# elec_connector.net
KiCad netlist of a schematic drawn in Altium Designer
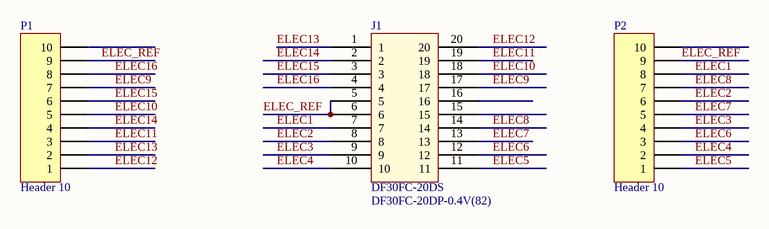
[diagram p0: elec_connector.SchDoc]

(export (version "E")
  (design (tool "Eeschema 10.0.6"))
  (components
    (comp (ref "J1")
      (value "DF30FC-20DS")
      (footprint "DF30FC-20DS")
      (description "CONN PLUG 20POS 0.4MM SMD GOLD")
      (fields
        (field (name "MANUFACTURER") "Hirose Electric Co Ltd")
        (field (name "MANUFACTURER PART NUMBER") "DF30FC-20DP-0.4V(82)")
      )
      (libsource (lib "custom") (part "DF30FC-20DP"))
    )
    (comp (ref "P1")
      (value "Header 10")
      (footprint "HDR1X10H")
      (description "Header, 10-Pin")
      (fields (field (name "PUBLISHER") "Altium Limited"))
      (libsource (lib "Miscellaneous Connectors") (part "Header 10"))
    )
    (comp (ref "P2")
      (value "Header 10")
      (footprint "HDR1X10")
      (description "Header, 10-Pin")
      (fields (field (name "PUBLISHER") "Altium Limited"))
      (libsource (lib "Miscellaneous Connectors") (part "Header 10"))
    )
  )
  (nets
    (net (code "1") (name "/ELEC1") (class "Default")
      (node (ref "J1") (pin "7") (pinfunction "7_7") (pintype "passive"))
      (node (ref "P2") (pin "8") (pinfunction "8_8") (pintype "passive"))
    )
    (net (code "2") (name "/ELEC2") (class "Default")
      (node (ref "J1") (pin "8") (pinfunction "8_8") (pintype "passive"))
      (node (ref "P2") (pin "6") (pinfunction "6_6") (pintype "passive"))
    )
    (net (code "3") (name "/ELEC3") (class "Default")
      (node (ref "J1") (pin "9") (pinfunction "9_9") (pintype "passive"))
      (node (ref "P2") (pin "4") (pinfunction "4_4") (pintype "passive"))
    )
    (net (code "4") (name "/ELEC4") (class "Default")
      (node (ref "J1") (pin "10") (pinfunction "10_10") (pintype "passive"))
      (node (ref "P2") (pin "2") (pinfunction "2_2") (pintype "passive"))
    )
    (net (code "5") (name "/ELEC5") (class "Default")
      (node (ref "J1") (pin "11") (pinfunction "11_11") (pintype "passive"))
      (node (ref "P2") (pin "1") (pinfunction "1_1") (pintype "passive"))
    )
    (net (code "6") (name "/ELEC6") (class "Default")
      (node (ref "J1") (pin "12") (pinfunction "12_12") (pintype "passive"))
      (node (ref "P2") (pin "3") (pinfunction "3_3") (pintype "passive"))
    )
    (net (code "7") (name "/ELEC7") (class "Default")
      (node (ref "J1") (pin "13") (pinfunction "13_13") (pintype "passive"))
      (node (ref "P2") (pin "5") (pinfunction "5_5") (pintype "passive"))
    )
    (net (code "8") (name "/ELEC8") (class "Default")
      (node (ref "J1") (pin "14") (pinfunction "14_14") (pintype "passive"))
      (node (ref "P2") (pin "7") (pinfunction "7_7") (pintype "passive"))
    )
    (net (code "9") (name "/ELEC9") (class "Default")
      (node (ref "J1") (pin "17") (pinfunction "17_17") (pintype "passive"))
      (node (ref "P1") (pin "7") (pinfunction "7_7") (pintype "passive"))
    )
    (net (code "10") (name "/ELEC10") (class "Default")
      (node (ref "J1") (pin "18") (pinfunction "18_18") (pintype "passive"))
      (node (ref "P1") (pin "5") (pinfunction "5_5") (pintype "passive"))
    )
    (net (code "11") (name "/ELEC11") (class "Default")
      (node (ref "J1") (pin "19") (pinfunction "19_19") (pintype "passive"))
      (node (ref "P1") (pin "3") (pinfunction "3_3") (pintype "passive"))
    )
    (net (code "12") (name "/ELEC12") (class "Default")
      (node (ref "J1") (pin "20") (pinfunction "20_20") (pintype "passive"))
      (node (ref "P1") (pin "1") (pinfunction "1_1") (pintype "passive"))
    )
    (net (code "13") (name "/ELEC13") (class "Default")
      (node (ref "J1") (pin "1") (pinfunction "1_1") (pintype "passive"))
      (node (ref "P1") (pin "2") (pinfunction "2_2") (pintype "passive"))
    )
    (net (code "14") (name "/ELEC14") (class "Default")
      (node (ref "J1") (pin "2") (pinfunction "2_2") (pintype "passive"))
      (node (ref "P1") (pin "4") (pinfunction "4_4") (pintype "passive"))
    )
    (net (code "15") (name "/ELEC15") (class "Default")
      (node (ref "J1") (pin "3") (pinfunction "3_3") (pintype "passive"))
      (node (ref "P1") (pin "6") (pinfunction "6_6") (pintype "passive"))
    )
    (net (code "16") (name "/ELEC16") (class "Default")
      (node (ref "J1") (pin "4") (pinfunction "4_4") (pintype "passive"))
      (node (ref "P1") (pin "8") (pinfunction "8_8") (pintype "passive"))
    )
    (net (code "17") (name "/ELEC_REF") (class "Default")
      (node (ref "J1") (pin "5") (pinfunction "5_5") (pintype "passive"))
      (node (ref "J1") (pin "6") (pinfunction "6_6") (pintype "passive"))
      (node (ref "P1") (pin "9") (pinfunction "9_9") (pintype "passive"))
      (node (ref "P2") (pin "9") (pinfunction "9_9") (pintype "passive"))
    )
    (net (code "18") (name "unconnected-(J1-Pad15)") (class "Default")
      (node (ref "J1") (pin "15") (pinfunction "15_15") (pintype "passive"))
    )
    (net (code "19") (name "unconnected-(J1-Pad16)") (class "Default")
      (node (ref "J1") (pin "16") (pinfunction "16_16") (pintype "passive"))
    )
    (net (code "20") (name "unconnected-(P1-Pad10)") (class "Default")
      (node (ref "P1") (pin "10") (pinfunction "10_10") (pintype "passive"))
    )
    (net (code "21") (name "unconnected-(P2-Pad10)") (class "Default")
      (node (ref "P2") (pin "10") (pinfunction "10_10") (pintype "passive"))
    )
  )
)
